# mysdramps.net
KiCad netlist of a schematic drawn in EAGLE
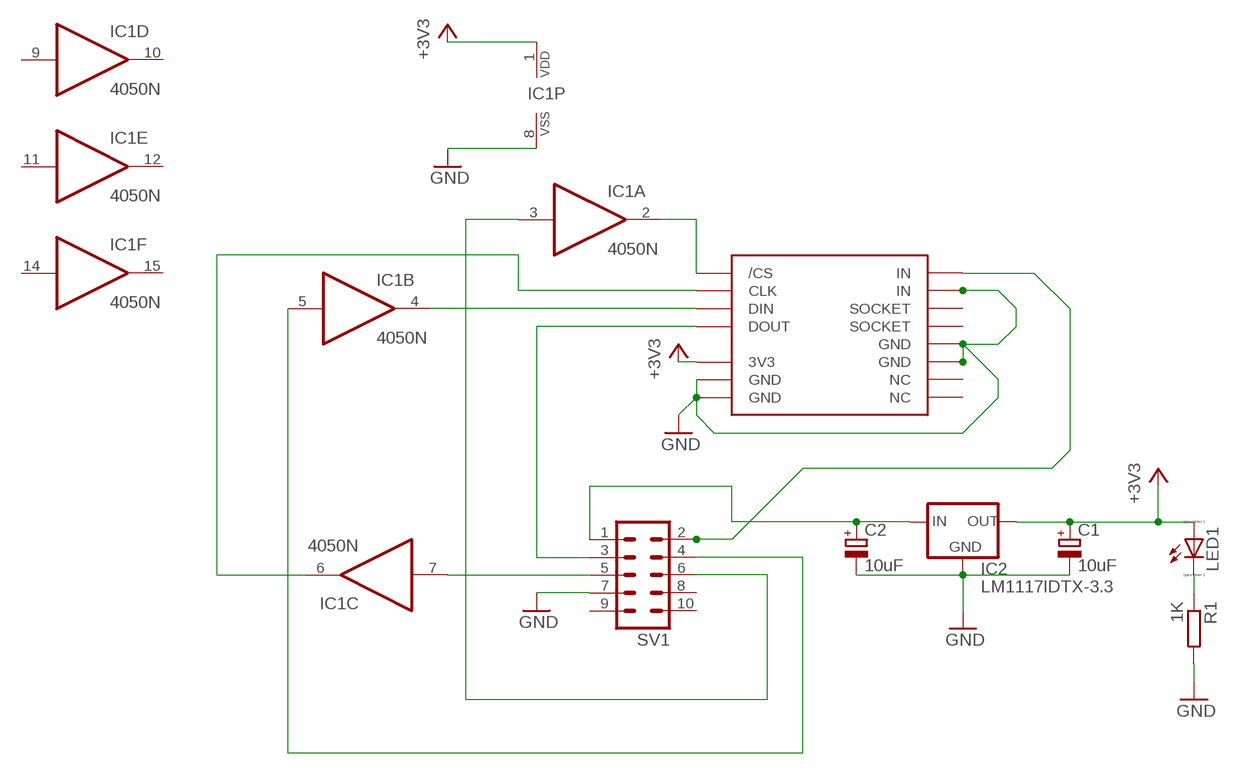
[diagram p0: schematic, sheet 1]

(export (version "E")
  (design (tool "Eeschema 10.0.6"))
  (components
    (comp (ref "C1")
      (value "10uF")
      (footprint "eagle-import:E5-5")
      (libsource (lib "eagle-import") (part "CPOL-EUE5-5"))
    )
    (comp (ref "C2")
      (value "10uF")
      (footprint "eagle-import:E5-5")
      (libsource (lib "eagle-import") (part "CPOL-EUE5-5"))
    )
    (comp (ref "IC1")
      (value "4050N")
      (footprint "eagle-import:DIL16")
      (libsource (lib "eagle-import") (part "4050N"))
    )
    (comp (ref "IC2")
      (value "LM1117IDTX-3.3")
      (footprint "eagle-import:TO252")
      (libsource (lib "eagle-import") (part "LM1117IDTX-3.3"))
    )
    (comp (ref "LED1")
      (value "LED_ELD260")
      (footprint "eagle-import:LED_LD260")
      (libsource (lib "eagle-import") (part "LED_ELD260"))
    )
    (comp (ref "R1")
      (value "1K")
      (footprint "eagle-import:0207_7")
      (libsource (lib "eagle-import") (part "R-EU_0207/7"))
    )
    (comp (ref "SV1")
      (value "MA05-2")
      (footprint "eagle-import:MA05-2")
      (libsource (lib "eagle-import") (part "MA05-2"))
    )
    (comp (ref "U$1")
      (value "MMC")
      (footprint "eagle-import:MMC_SOCKET")
      (libsource (lib "eagle-import") (part "MMC"))
    )
  )
  (nets
    (net (code "1") (name "+3V3") (class "Default")
      (node (ref "C1") (pin "+") (pinfunction "+_+") (pintype "passive"))
      (node (ref "IC1") (pin "1") (pinfunction "VDD_1") (pintype "power_in"))
      (node (ref "IC2") (pin "TAB") (pinfunction "OUT_TAB") (pintype "passive"))
      (node (ref "LED1") (pin "A") (pinfunction "A_A") (pintype "passive"))
      (node (ref "U$1") (pin "3V3") (pinfunction "3V3_3V3") (pintype "power_in"))
    )
    (net (code "2") (name "GND") (class "Default")
      (node (ref "C1") (pin "-") (pinfunction "-_-") (pintype "passive"))
      (node (ref "C2") (pin "-") (pinfunction "-_-") (pintype "passive"))
      (node (ref "IC1") (pin "8") (pinfunction "VSS_8") (pintype "power_in"))
      (node (ref "IC2") (pin "1") (pinfunction "GND_1") (pintype "input"))
      (node (ref "R1") (pin "2") (pinfunction "2_2") (pintype "passive"))
      (node (ref "SV1") (pin "7") (pinfunction "7_7") (pintype "passive"))
      (node (ref "U$1") (pin "GND@1") (pinfunction "GND_GND@1") (pintype "power_in"))
      (node (ref "U$1") (pin "GND@2") (pinfunction "GND_GND@2") (pintype "power_in"))
      (node (ref "U$1") (pin "GND@3") (pinfunction "GND_GND@3") (pintype "power_in"))
      (node (ref "U$1") (pin "GND@4") (pinfunction "GND_GND@4") (pintype "power_in"))
      (node (ref "U$1") (pin "IN@2") (pinfunction "IN_IN@2") (pintype "input"))
    )
    (net (code "3") (name "Net-(IC1A-I)") (class "Default")
      (node (ref "IC1") (pin "3") (pinfunction "I_3") (pintype "input"))
      (node (ref "SV1") (pin "6") (pinfunction "6_6") (pintype "passive"))
    )
    (net (code "4") (name "Net-(IC1A-O)") (class "Default")
      (node (ref "IC1") (pin "2") (pinfunction "O_2") (pintype "output"))
      (node (ref "U$1") (pin "/CS") (pinfunction "/CS_/CS") (pintype "input"))
    )
    (net (code "5") (name "Net-(IC1B-I)") (class "Default")
      (node (ref "IC1") (pin "5") (pinfunction "I_5") (pintype "input"))
      (node (ref "SV1") (pin "4") (pinfunction "4_4") (pintype "passive"))
    )
    (net (code "6") (name "Net-(IC1B-O)") (class "Default")
      (node (ref "IC1") (pin "4") (pinfunction "O_4") (pintype "output"))
      (node (ref "U$1") (pin "DIN") (pinfunction "DIN_DIN") (pintype "input"))
    )
    (net (code "7") (name "Net-(IC1C-I)") (class "Default")
      (node (ref "IC1") (pin "7") (pinfunction "I_7") (pintype "input"))
      (node (ref "SV1") (pin "5") (pinfunction "5_5") (pintype "passive"))
    )
    (net (code "8") (name "Net-(IC1C-O)") (class "Default")
      (node (ref "IC1") (pin "6") (pinfunction "O_6") (pintype "output"))
      (node (ref "U$1") (pin "CLK") (pinfunction "CLK_CLK") (pintype "input"))
    )
    (net (code "9") (name "Net-(IC2-IN)") (class "Default")
      (node (ref "C2") (pin "+") (pinfunction "+_+") (pintype "passive"))
      (node (ref "IC2") (pin "2") (pinfunction "IN_2") (pintype "input"))
      (node (ref "SV1") (pin "1") (pinfunction "1_1") (pintype "passive"))
    )
    (net (code "10") (name "Net-(LED1-C)") (class "Default")
      (node (ref "LED1") (pin "K") (pinfunction "C_K") (pintype "passive"))
      (node (ref "R1") (pin "1") (pinfunction "1_1") (pintype "passive"))
    )
    (net (code "11") (name "Net-(SV1-Pad2)") (class "Default")
      (node (ref "SV1") (pin "2") (pinfunction "2_2") (pintype "passive"))
      (node (ref "U$1") (pin "IN@1") (pinfunction "IN_IN@1") (pintype "input"))
    )
    (net (code "12") (name "Net-(SV1-Pad3)") (class "Default")
      (node (ref "SV1") (pin "3") (pinfunction "3_3") (pintype "passive"))
      (node (ref "U$1") (pin "DOUT") (pinfunction "DOUT_DOUT") (pintype "output"))
    )
    (net (code "13") (name "unconnected-(IC1D-I-Pad9)") (class "Default")
      (node (ref "IC1") (pin "9") (pinfunction "I_9") (pintype "input"))
    )
    (net (code "14") (name "unconnected-(IC1D-O-Pad10)") (class "Default")
      (node (ref "IC1") (pin "10") (pinfunction "O_10") (pintype "output"))
    )
    (net (code "15") (name "unconnected-(IC1E-I-Pad11)") (class "Default")
      (node (ref "IC1") (pin "11") (pinfunction "I_11") (pintype "input"))
    )
    (net (code "16") (name "unconnected-(IC1E-O-Pad12)") (class "Default")
      (node (ref "IC1") (pin "12") (pinfunction "O_12") (pintype "output"))
    )
    (net (code "17") (name "unconnected-(IC1F-I-Pad14)") (class "Default")
      (node (ref "IC1") (pin "14") (pinfunction "I_14") (pintype "input"))
    )
    (net (code "18") (name "unconnected-(IC1F-O-Pad15)") (class "Default")
      (node (ref "IC1") (pin "15") (pinfunction "O_15") (pintype "output"))
    )
    (net (code "19") (name "unconnected-(SV1-Pad8)") (class "Default")
      (node (ref "SV1") (pin "8") (pinfunction "8_8") (pintype "passive"))
    )
    (net (code "20") (name "unconnected-(SV1-Pad9)") (class "Default")
      (node (ref "SV1") (pin "9") (pinfunction "9_9") (pintype "passive"))
    )
    (net (code "21") (name "unconnected-(SV1-Pad10)") (class "Default")
      (node (ref "SV1") (pin "10") (pinfunction "10_10") (pintype "passive"))
    )
    (net (code "22") (name "unconnected-(U$1-NC-PadNC@1)") (class "Default")
      (node (ref "U$1") (pin "NC@1") (pinfunction "NC_NC@1") (pintype "no_connect"))
    )
    (net (code "23") (name "unconnected-(U$1-NC-PadNC@2)") (class "Default")
      (node (ref "U$1") (pin "NC@2") (pinfunction "NC_NC@2") (pintype "no_connect"))
    )
    (net (code "24") (name "unconnected-(U$1-SOCKET-PadP$1)") (class "Default")
      (node (ref "U$1") (pin "P$1") (pinfunction "SOCKET_P$1") (pintype "input"))
    )
    (net (code "25") (name "unconnected-(U$1-SOCKET-PadP$2)") (class "Default")
      (node (ref "U$1") (pin "P$2") (pinfunction "SOCKET_P$2") (pintype "input"))
    )
  )
)
